# PIC18F4431_Dev_Board.net
KiCad netlist of a schematic drawn in EAGLE
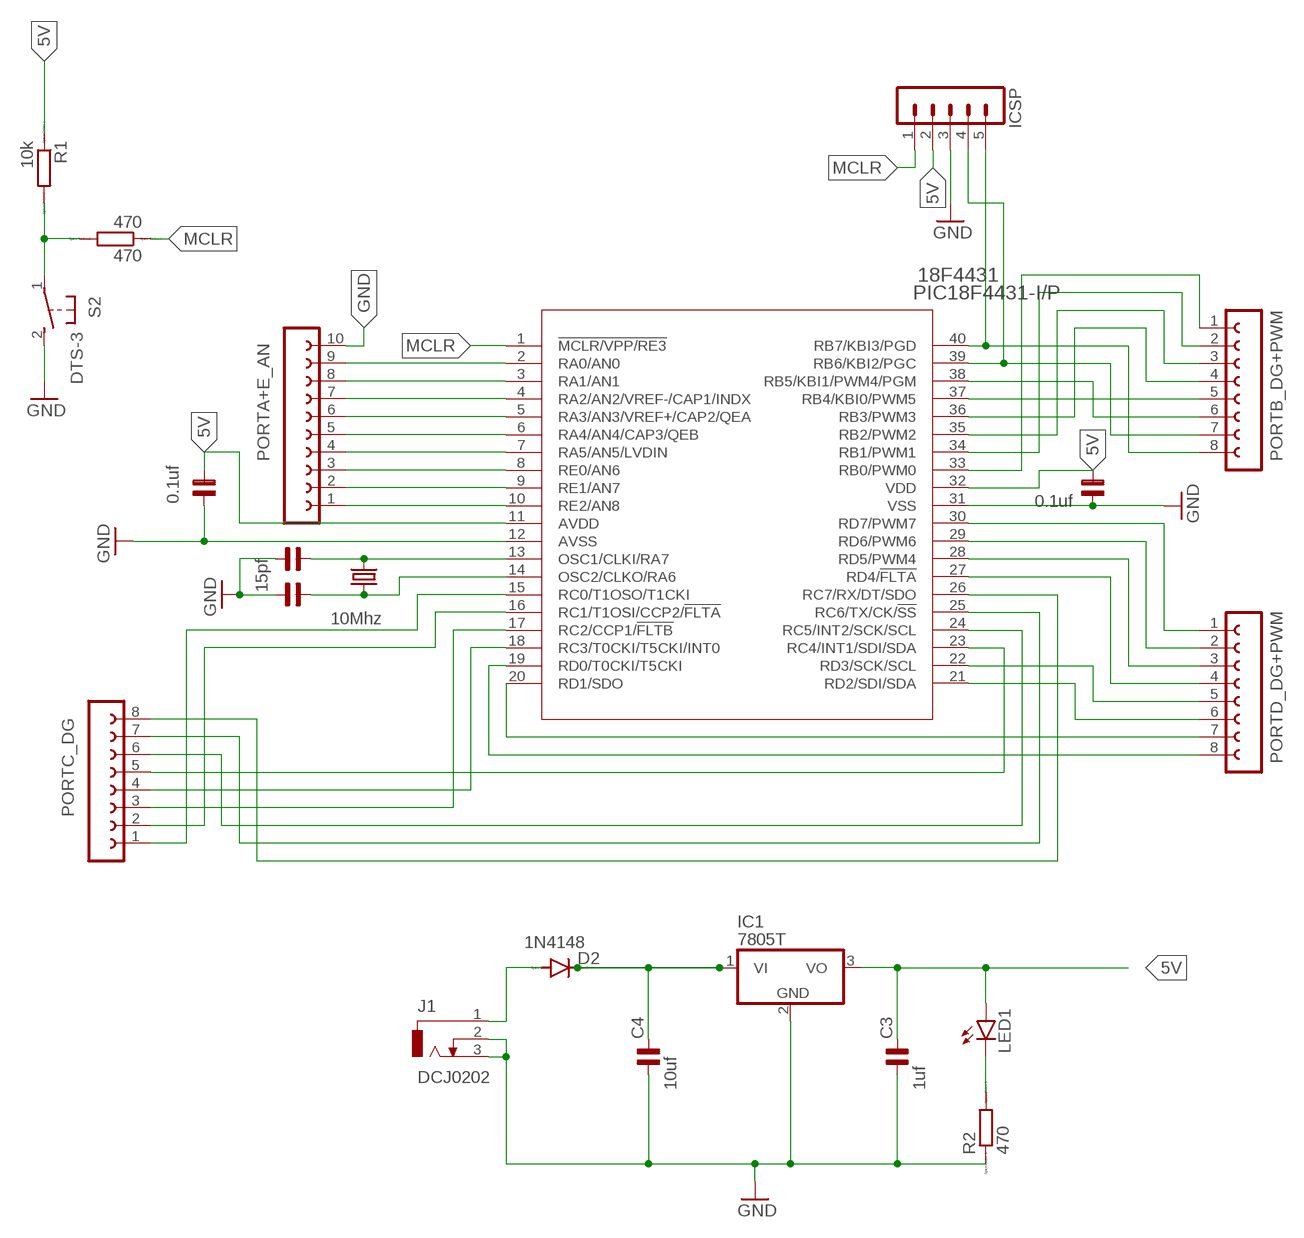
[diagram p0: schematic, sheet 1]

(export (version "E")
  (design (tool "Eeschema 10.0.6"))
  (components
    (comp (ref "18F4431")
      (value "PIC18F4431-I/P")
      (footprint "eagle-import:PDIP40_600MC")
      (fields (field (name "MANUFACTURER_PART_NUMBER") "PIC18F4431IP"))
      (libsource (lib "eagle-import") (part "PIC18F4431-I/P"))
    )
    (comp (ref "470")
      (value "470")
      (footprint "eagle-import:0207_10")
      (libsource (lib "eagle-import") (part "R0207/10"))
    )
    (comp (ref "C1")
      (value "15pf")
      (footprint "eagle-import:ENP1,5-4")
      (libsource (lib "eagle-import") (part "C-BP-1,5X4"))
    )
    (comp (ref "C2")
      (value "15pf")
      (footprint "eagle-import:ENP1,5-4")
      (libsource (lib "eagle-import") (part "C-BP-1,5X4"))
    )
    (comp (ref "C3")
      (value "1uf")
      (footprint "eagle-import:ENP1,5-4")
      (libsource (lib "eagle-import") (part "C-BP-1,5X4"))
    )
    (comp (ref "C4")
      (value "10uf")
      (footprint "eagle-import:ENP1,5-4")
      (libsource (lib "eagle-import") (part "C-BP-1,5X4"))
    )
    (comp (ref "C5")
      (value "0.1uf")
      (footprint "eagle-import:ENP1,5-4")
      (libsource (lib "eagle-import") (part "C-BP-1,5X4"))
    )
    (comp (ref "C6")
      (value "0.1uf")
      (footprint "eagle-import:ENP1,5-4")
      (libsource (lib "eagle-import") (part "C-BP-1,5X4"))
    )
    (comp (ref "D2")
      (value "1N4148")
      (footprint "eagle-import:DO35-7")
      (libsource (lib "eagle-import") (part "1N4148DO35-7"))
    )
    (comp (ref "IC1")
      (value "7805T")
      (footprint "eagle-import:TO220H")
      (libsource (lib "eagle-import") (part "78T05"))
    )
    (comp (ref "ICSP")
      (value "MA05-1")
      (footprint "eagle-import:MA05-1")
      (libsource (lib "eagle-import") (part "MA05-1"))
    )
    (comp (ref "J1")
      (value "DCJ0202")
      (footprint "eagle-import:DCJ0202")
      (libsource (lib "eagle-import") (part "DCJ0202"))
    )
    (comp (ref "LED1")
      (value "LED5MM")
      (footprint "eagle-import:LED5MM")
      (libsource (lib "eagle-import") (part "LED5MM"))
    )
    (comp (ref "PORTA+E_AN")
      (value "FE10-1")
      (footprint "eagle-import:FE10")
      (libsource (lib "eagle-import") (part "FE10-1"))
    )
    (comp (ref "PORTB_DG+PWM")
      (value "FE08-1")
      (footprint "eagle-import:FE08")
      (libsource (lib "eagle-import") (part "FE08-1"))
    )
    (comp (ref "PORTC_DG")
      (value "FE08-1")
      (footprint "eagle-import:FE08")
      (libsource (lib "eagle-import") (part "FE08-1"))
    )
    (comp (ref "PORTD_DG+PWM")
      (value "FE08-1")
      (footprint "eagle-import:FE08")
      (libsource (lib "eagle-import") (part "FE08-1"))
    )
    (comp (ref "Q2")
      (value "10Mhz")
      (footprint "eagle-import:HC49_S")
      (libsource (lib "eagle-import") (part "CRYSTALHC49S"))
    )
    (comp (ref "R1")
      (value "10k")
      (footprint "eagle-import:0207_10")
      (libsource (lib "eagle-import") (part "R0207/10"))
    )
    (comp (ref "R2")
      (value "470")
      (footprint "eagle-import:0207_10")
      (libsource (lib "eagle-import") (part "R0207/10"))
    )
    (comp (ref "S2")
      (value "DTS-3")
      (footprint "eagle-import:DTS-3")
      (libsource (lib "eagle-import") (part "DTS-3"))
    )
  )
  (nets
    (net (code "1") (name "5V") (class "Default")
      (node (ref "18F4431") (pin "11") (pinfunction "AVDD_11") (pintype "passive"))
      (node (ref "18F4431") (pin "32") (pinfunction "VDD_32") (pintype "passive"))
      (node (ref "C3") (pin "2") (pinfunction "2_2") (pintype "passive"))
      (node (ref "C5") (pin "2") (pinfunction "2_2") (pintype "passive"))
      (node (ref "C6") (pin "2") (pinfunction "2_2") (pintype "passive"))
      (node (ref "IC1") (pin "3") (pinfunction "VO_3") (pintype "passive"))
      (node (ref "ICSP") (pin "2") (pinfunction "2_2") (pintype "passive"))
      (node (ref "LED1") (pin "A") (pinfunction "A_A") (pintype "passive"))
      (node (ref "R1") (pin "1") (pinfunction "1_1") (pintype "passive"))
    )
    (net (code "2") (name "GND") (class "Default")
      (node (ref "18F4431") (pin "12") (pinfunction "AVSS_12") (pintype "passive"))
      (node (ref "18F4431") (pin "31") (pinfunction "VSS_31") (pintype "passive"))
      (node (ref "C1") (pin "1") (pinfunction "1_1") (pintype "passive"))
      (node (ref "C2") (pin "1") (pinfunction "1_1") (pintype "passive"))
      (node (ref "C3") (pin "1") (pinfunction "1_1") (pintype "passive"))
      (node (ref "C4") (pin "1") (pinfunction "1_1") (pintype "passive"))
      (node (ref "C5") (pin "1") (pinfunction "1_1") (pintype "passive"))
      (node (ref "C6") (pin "1") (pinfunction "1_1") (pintype "passive"))
      (node (ref "IC1") (pin "2") (pinfunction "GND_2") (pintype "passive"))
      (node (ref "ICSP") (pin "3") (pinfunction "3_3") (pintype "passive"))
      (node (ref "J1") (pin "2") (pinfunction "2_2") (pintype "passive"))
      (node (ref "J1") (pin "3") (pinfunction "3_3") (pintype "passive"))
      (node (ref "PORTA+E_AN") (pin "10") (pinfunction "10_10") (pintype "passive"))
      (node (ref "R2") (pin "1") (pinfunction "1_1") (pintype "passive"))
      (node (ref "S2") (pin "2") (pinfunction "2_2") (pintype "passive"))
    )
    (net (code "3") (name "MCLR") (class "Default")
      (node (ref "18F4431") (pin "1") (pinfunction "~{MCLR/VPP/RE3}_1") (pintype "passive"))
      (node (ref "470") (pin "1") (pinfunction "1_1") (pintype "passive"))
      (node (ref "ICSP") (pin "1") (pinfunction "1_1") (pintype "passive"))
    )
    (net (code "4") (name "Net-(18F4431-OSC1{slash}CLKI{slash}RA7)") (class "Default")
      (node (ref "18F4431") (pin "13") (pinfunction "OSC1/CLKI/RA7_13") (pintype "passive"))
      (node (ref "C1") (pin "2") (pinfunction "2_2") (pintype "passive"))
      (node (ref "Q2") (pin "2") (pinfunction "2_2") (pintype "passive"))
    )
    (net (code "5") (name "Net-(18F4431-OSC2{slash}CLKO{slash}RA6)") (class "Default")
      (node (ref "18F4431") (pin "14") (pinfunction "OSC2/CLKO/RA6_14") (pintype "passive"))
      (node (ref "C2") (pin "2") (pinfunction "2_2") (pintype "passive"))
      (node (ref "Q2") (pin "1") (pinfunction "1_1") (pintype "passive"))
    )
    (net (code "6") (name "Net-(18F4431-RA0{slash}AN0)") (class "Default")
      (node (ref "18F4431") (pin "2") (pinfunction "RA0/AN0_2") (pintype "passive"))
      (node (ref "PORTA+E_AN") (pin "9") (pinfunction "9_9") (pintype "passive"))
    )
    (net (code "7") (name "Net-(18F4431-RA1{slash}AN1)") (class "Default")
      (node (ref "18F4431") (pin "3") (pinfunction "RA1/AN1_3") (pintype "passive"))
      (node (ref "PORTA+E_AN") (pin "8") (pinfunction "8_8") (pintype "passive"))
    )
    (net (code "8") (name "Net-(18F4431-RA2{slash}AN2{slash}VREF-{slash}CAP1{slash}INDX)") (class "Default")
      (node (ref "18F4431") (pin "4") (pinfunction "RA2/AN2/VREF-/CAP1/INDX_4") (pintype "passive"))
      (node (ref "PORTA+E_AN") (pin "7") (pinfunction "7_7") (pintype "passive"))
    )
    (net (code "9") (name "Net-(18F4431-RA3{slash}AN3{slash}VREF+{slash}CAP2{slash}QEA)") (class "Default")
      (node (ref "18F4431") (pin "5") (pinfunction "RA3/AN3/VREF+/CAP2/QEA_5") (pintype "passive"))
      (node (ref "PORTA+E_AN") (pin "6") (pinfunction "6_6") (pintype "passive"))
    )
    (net (code "10") (name "Net-(18F4431-RA4{slash}AN4{slash}CAP3{slash}QEB)") (class "Default")
      (node (ref "18F4431") (pin "6") (pinfunction "RA4/AN4/CAP3/QEB_6") (pintype "passive"))
      (node (ref "PORTA+E_AN") (pin "5") (pinfunction "5_5") (pintype "passive"))
    )
    (net (code "11") (name "Net-(18F4431-RA5{slash}AN5{slash}LVDIN)") (class "Default")
      (node (ref "18F4431") (pin "7") (pinfunction "RA5/AN5/LVDIN_7") (pintype "passive"))
      (node (ref "PORTA+E_AN") (pin "4") (pinfunction "4_4") (pintype "passive"))
    )
    (net (code "12") (name "Net-(18F4431-RB0{slash}PWM0)") (class "Default")
      (node (ref "18F4431") (pin "33") (pinfunction "RB0/PWM0_33") (pintype "passive"))
      (node (ref "PORTB_DG+PWM") (pin "1") (pinfunction "1_1") (pintype "passive"))
    )
    (net (code "13") (name "Net-(18F4431-RB1{slash}PWM1)") (class "Default")
      (node (ref "18F4431") (pin "34") (pinfunction "RB1/PWM1_34") (pintype "passive"))
      (node (ref "PORTB_DG+PWM") (pin "2") (pinfunction "2_2") (pintype "passive"))
    )
    (net (code "14") (name "Net-(18F4431-RB2{slash}PWM2)") (class "Default")
      (node (ref "18F4431") (pin "35") (pinfunction "RB2/PWM2_35") (pintype "passive"))
      (node (ref "PORTB_DG+PWM") (pin "3") (pinfunction "3_3") (pintype "passive"))
    )
    (net (code "15") (name "Net-(18F4431-RB3{slash}PWM3)") (class "Default")
      (node (ref "18F4431") (pin "36") (pinfunction "RB3/PWM3_36") (pintype "passive"))
      (node (ref "PORTB_DG+PWM") (pin "4") (pinfunction "4_4") (pintype "passive"))
    )
    (net (code "16") (name "Net-(18F4431-RB4{slash}KBI0{slash}PWM5)") (class "Default")
      (node (ref "18F4431") (pin "37") (pinfunction "RB4/KBI0/PWM5_37") (pintype "passive"))
      (node (ref "PORTB_DG+PWM") (pin "5") (pinfunction "5_5") (pintype "passive"))
    )
    (net (code "17") (name "Net-(18F4431-RB5{slash}KBI1{slash}PWM4{slash}PGM)") (class "Default")
      (node (ref "18F4431") (pin "38") (pinfunction "RB5/KBI1/PWM4/PGM_38") (pintype "passive"))
      (node (ref "PORTB_DG+PWM") (pin "6") (pinfunction "6_6") (pintype "passive"))
    )
    (net (code "18") (name "Net-(18F4431-RB6{slash}KBI2{slash}PGC)") (class "Default")
      (node (ref "18F4431") (pin "39") (pinfunction "RB6/KBI2/PGC_39") (pintype "passive"))
      (node (ref "ICSP") (pin "4") (pinfunction "4_4") (pintype "passive"))
      (node (ref "PORTB_DG+PWM") (pin "7") (pinfunction "7_7") (pintype "passive"))
    )
    (net (code "19") (name "Net-(18F4431-RB7{slash}KBI3{slash}PGD)") (class "Default")
      (node (ref "18F4431") (pin "40") (pinfunction "RB7/KBI3/PGD_40") (pintype "passive"))
      (node (ref "ICSP") (pin "5") (pinfunction "5_5") (pintype "passive"))
      (node (ref "PORTB_DG+PWM") (pin "8") (pinfunction "8_8") (pintype "passive"))
    )
    (net (code "20") (name "Net-(18F4431-RC0{slash}T1OSO{slash}T1CKI)") (class "Default")
      (node (ref "18F4431") (pin "15") (pinfunction "RC0/T1OSO/T1CKI_15") (pintype "passive"))
      (node (ref "PORTC_DG") (pin "1") (pinfunction "1_1") (pintype "passive"))
    )
    (net (code "21") (name "Net-(18F4431-RC1{slash}T1OSI{slash}CCP2{slash}~{FLTA})") (class "Default")
      (node (ref "18F4431") (pin "16") (pinfunction "RC1/T1OSI/CCP2/~{FLTA}_16") (pintype "passive"))
      (node (ref "PORTC_DG") (pin "2") (pinfunction "2_2") (pintype "passive"))
    )
    (net (code "22") (name "Net-(18F4431-RC2{slash}CCP1{slash}~{FLTB})") (class "Default")
      (node (ref "18F4431") (pin "17") (pinfunction "RC2/CCP1/~{FLTB}_17") (pintype "passive"))
      (node (ref "PORTC_DG") (pin "3") (pinfunction "3_3") (pintype "passive"))
    )
    (net (code "23") (name "Net-(18F4431-RC3{slash}T0CKI{slash}T5CKI{slash}INT0)") (class "Default")
      (node (ref "18F4431") (pin "18") (pinfunction "RC3/T0CKI/T5CKI/INT0_18") (pintype "passive"))
      (node (ref "PORTC_DG") (pin "4") (pinfunction "4_4") (pintype "passive"))
    )
    (net (code "24") (name "Net-(18F4431-RC4{slash}INT1{slash}SDI{slash}SDA)") (class "Default")
      (node (ref "18F4431") (pin "23") (pinfunction "RC4/INT1/SDI/SDA_23") (pintype "passive"))
      (node (ref "PORTC_DG") (pin "5") (pinfunction "5_5") (pintype "passive"))
    )
    (net (code "25") (name "Net-(18F4431-RC5{slash}INT2{slash}SCK{slash}SCL)") (class "Default")
      (node (ref "18F4431") (pin "24") (pinfunction "RC5/INT2/SCK/SCL_24") (pintype "passive"))
      (node (ref "PORTC_DG") (pin "6") (pinfunction "6_6") (pintype "passive"))
    )
    (net (code "26") (name "Net-(18F4431-RC6{slash}TX{slash}CK{slash}~{SS})") (class "Default")
      (node (ref "18F4431") (pin "25") (pinfunction "RC6/TX/CK/~{SS}_25") (pintype "passive"))
      (node (ref "PORTC_DG") (pin "7") (pinfunction "7_7") (pintype "passive"))
    )
    (net (code "27") (name "Net-(18F4431-RC7{slash}RX{slash}DT{slash}SDO)") (class "Default")
      (node (ref "18F4431") (pin "26") (pinfunction "RC7/RX/DT/SDO_26") (pintype "passive"))
      (node (ref "PORTC_DG") (pin "8") (pinfunction "8_8") (pintype "passive"))
    )
    (net (code "28") (name "Net-(18F4431-RD0{slash}T0CKI{slash}T5CKI)") (class "Default")
      (node (ref "18F4431") (pin "19") (pinfunction "RD0/T0CKI/T5CKI_19") (pintype "passive"))
      (node (ref "PORTD_DG+PWM") (pin "8") (pinfunction "8_8") (pintype "passive"))
    )
    (net (code "29") (name "Net-(18F4431-RD1{slash}SDO)") (class "Default")
      (node (ref "18F4431") (pin "20") (pinfunction "RD1/SDO_20") (pintype "passive"))
      (node (ref "PORTD_DG+PWM") (pin "7") (pinfunction "7_7") (pintype "passive"))
    )
    (net (code "30") (name "Net-(18F4431-RD2{slash}SDI{slash}SDA)") (class "Default")
      (node (ref "18F4431") (pin "21") (pinfunction "RD2/SDI/SDA_21") (pintype "passive"))
      (node (ref "PORTD_DG+PWM") (pin "6") (pinfunction "6_6") (pintype "passive"))
    )
    (net (code "31") (name "Net-(18F4431-RD3{slash}SCK{slash}SCL)") (class "Default")
      (node (ref "18F4431") (pin "22") (pinfunction "RD3/SCK/SCL_22") (pintype "passive"))
      (node (ref "PORTD_DG+PWM") (pin "5") (pinfunction "5_5") (pintype "passive"))
    )
    (net (code "32") (name "Net-(18F4431-RD4{slash}~{FLTA})") (class "Default")
      (node (ref "18F4431") (pin "27") (pinfunction "RD4/~{FLTA}_27") (pintype "passive"))
      (node (ref "PORTD_DG+PWM") (pin "4") (pinfunction "4_4") (pintype "passive"))
    )
    (net (code "33") (name "Net-(18F4431-RD5{slash}PWM4)") (class "Default")
      (node (ref "18F4431") (pin "28") (pinfunction "RD5/PWM4_28") (pintype "passive"))
      (node (ref "PORTD_DG+PWM") (pin "3") (pinfunction "3_3") (pintype "passive"))
    )
    (net (code "34") (name "Net-(18F4431-RD6{slash}PWM6)") (class "Default")
      (node (ref "18F4431") (pin "29") (pinfunction "RD6/PWM6_29") (pintype "passive"))
      (node (ref "PORTD_DG+PWM") (pin "2") (pinfunction "2_2") (pintype "passive"))
    )
    (net (code "35") (name "Net-(18F4431-RD7{slash}PWM7)") (class "Default")
      (node (ref "18F4431") (pin "30") (pinfunction "RD7/PWM7_30") (pintype "passive"))
      (node (ref "PORTD_DG+PWM") (pin "1") (pinfunction "1_1") (pintype "passive"))
    )
    (net (code "36") (name "Net-(18F4431-RE0{slash}AN6)") (class "Default")
      (node (ref "18F4431") (pin "8") (pinfunction "RE0/AN6_8") (pintype "passive"))
      (node (ref "PORTA+E_AN") (pin "3") (pinfunction "3_3") (pintype "passive"))
    )
    (net (code "37") (name "Net-(18F4431-RE1{slash}AN7)") (class "Default")
      (node (ref "18F4431") (pin "9") (pinfunction "RE1/AN7_9") (pintype "passive"))
      (node (ref "PORTA+E_AN") (pin "2") (pinfunction "2_2") (pintype "passive"))
    )
    (net (code "38") (name "Net-(18F4431-RE2{slash}AN8)") (class "Default")
      (node (ref "18F4431") (pin "10") (pinfunction "RE2/AN8_10") (pintype "passive"))
      (node (ref "PORTA+E_AN") (pin "1") (pinfunction "1_1") (pintype "passive"))
    )
    (net (code "39") (name "Net-(470-Pad2)") (class "Default")
      (node (ref "470") (pin "2") (pinfunction "2_2") (pintype "passive"))
      (node (ref "R1") (pin "2") (pinfunction "2_2") (pintype "passive"))
      (node (ref "S2") (pin "1") (pinfunction "1_1") (pintype "passive"))
    )
    (net (code "40") (name "Net-(D2-PadA)") (class "Default")
      (node (ref "D2") (pin "A") (pinfunction "A_A") (pintype "passive"))
      (node (ref "J1") (pin "1") (pinfunction "1_1") (pintype "passive"))
    )
    (net (code "41") (name "Net-(IC1-VI)") (class "Default")
      (node (ref "C4") (pin "2") (pinfunction "2_2") (pintype "passive"))
      (node (ref "D2") (pin "C") (pinfunction "C_C") (pintype "passive"))
      (node (ref "IC1") (pin "1") (pinfunction "VI_1") (pintype "input"))
    )
    (net (code "42") (name "Net-(LED1-C)") (class "Default")
      (node (ref "LED1") (pin "K") (pinfunction "C_K") (pintype "passive"))
      (node (ref "R2") (pin "2") (pinfunction "2_2") (pintype "passive"))
    )
  )
)
